# BAD.net
KiCad netlist of a schematic drawn in EAGLE
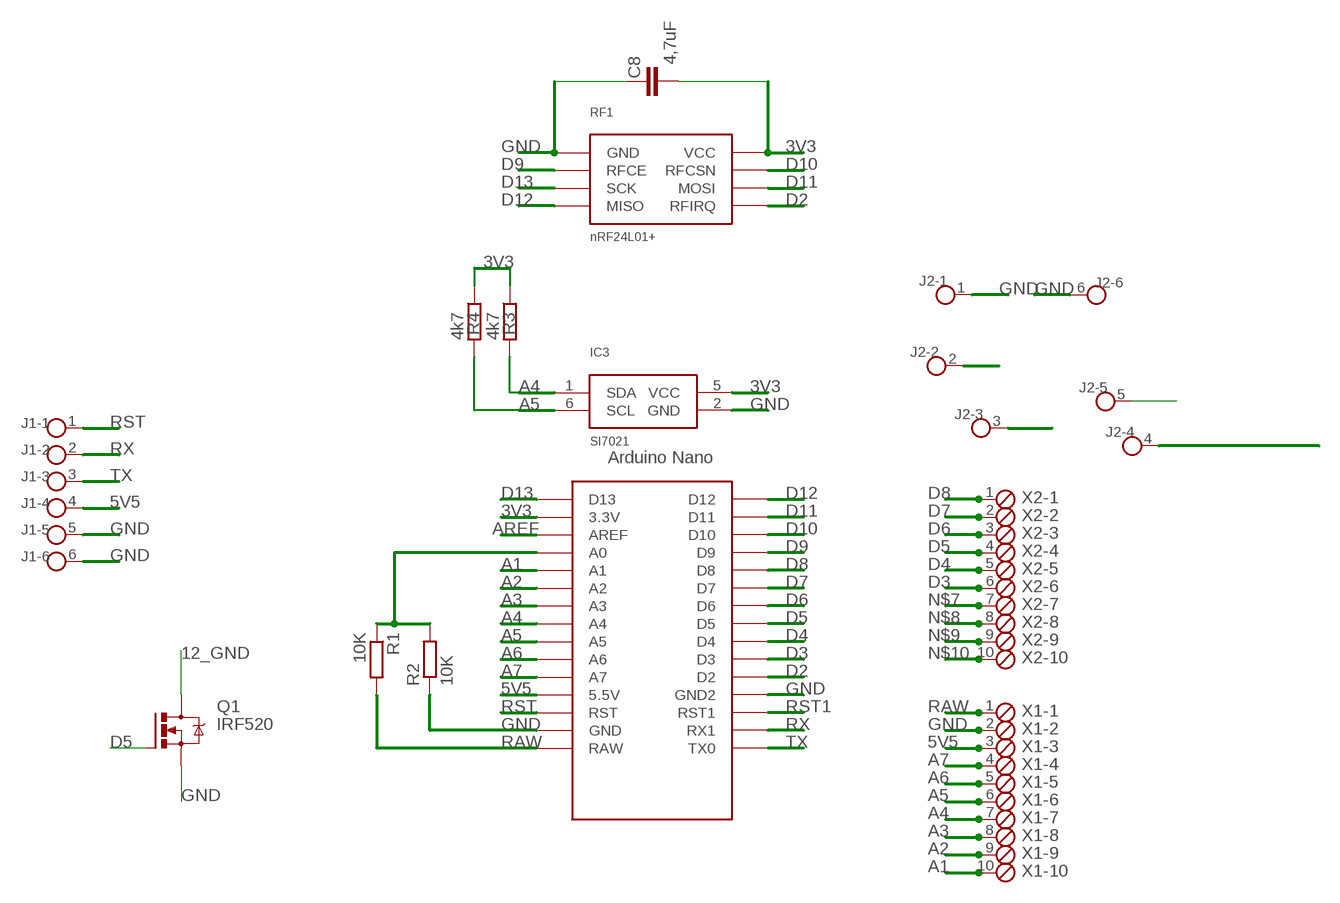
[diagram p0: schematic, sheet 1]

(export (version "E")
  (design (tool "Eeschema 10.0.6"))
  (components
    (comp (ref "C8")
      (value "4,7uF")
      (footprint "eagle-import:C3216")
      (libsource (lib "eagle-import") (part "C-EUC3216"))
    )
    (comp (ref "IC3")
      (value "SI7021")
      (footprint "eagle-import:DFN6")
      (libsource (lib "eagle-import") (part "SI7021"))
    )
    (comp (ref "J1")
      (value "FTDI")
      (footprint "eagle-import:LIST6B")
      (libsource (lib "eagle-import") (part "LIST6LIST6B"))
    )
    (comp (ref "J2")
      (value "LIST6")
      (footprint "eagle-import:LIST6")
      (libsource (lib "eagle-import") (part "LIST6"))
    )
    (comp (ref "Q1")
      (value "IRF520")
      (footprint "eagle-import:TO220BV")
      (libsource (lib "eagle-import") (part "IRF520"))
    )
    (comp (ref "R1")
      (value "10K")
      (footprint "eagle-import:R0805")
      (libsource (lib "eagle-import") (part "R-EU_R0805"))
    )
    (comp (ref "R2")
      (value "10K")
      (footprint "eagle-import:R0805")
      (libsource (lib "eagle-import") (part "R-EU_R0805"))
    )
    (comp (ref "R3")
      (value "4k7")
      (footprint "eagle-import:R0805")
      (libsource (lib "eagle-import") (part "R-EU_R0805"))
    )
    (comp (ref "R4")
      (value "4k7")
      (footprint "eagle-import:R0805")
      (libsource (lib "eagle-import") (part "R-EU_R0805"))
    )
    (comp (ref "RF1")
      (value "nRF24L01+")
      (footprint "eagle-import:2X4-2.54MM")
      (libsource (lib "eagle-import") (part "NRF24L01"))
    )
    (comp (ref "U$1")
      (value "NANO")
      (footprint "eagle-import:NANO")
      (libsource (lib "eagle-import") (part "NANO"))
    )
    (comp (ref "X1")
      (value "MPT10")
      (footprint "eagle-import:10POL254")
      (libsource (lib "eagle-import") (part "MPT10"))
    )
    (comp (ref "X2")
      (value "MPT10")
      (footprint "eagle-import:10POL254")
      (libsource (lib "eagle-import") (part "MPT10"))
    )
  )
  (nets
    (net (code "1") (name "/3V3") (class "Default")
      (node (ref "C8") (pin "1") (pinfunction "1_1") (pintype "passive"))
      (node (ref "IC3") (pin "5") (pinfunction "VCC_5") (pintype "bidirectional"))
      (node (ref "J2") (pin "2") (pinfunction "1_2") (pintype "passive"))
      (node (ref "R3") (pin "1") (pinfunction "1_1") (pintype "passive"))
      (node (ref "R4") (pin "1") (pinfunction "1_1") (pintype "passive"))
      (node (ref "RF1") (pin "P$2") (pinfunction "VCC_P$2") (pintype "power_in"))
      (node (ref "U$1") (pin "3.3V") (pinfunction "3.3V_3.3V") (pintype "bidirectional"))
    )
    (net (code "2") (name "/5V5") (class "Default")
      (node (ref "J1") (pin "4") (pinfunction "1_4") (pintype "passive"))
      (node (ref "J2") (pin "3") (pinfunction "1_3") (pintype "passive"))
      (node (ref "U$1") (pin "5V") (pinfunction "5.5V_5V") (pintype "bidirectional"))
      (node (ref "X1") (pin "3") (pinfunction "1_3") (pintype "passive"))
    )
    (net (code "3") (name "/12_GND") (class "Default")
      (node (ref "J2") (pin "5") (pinfunction "1_5") (pintype "passive"))
      (node (ref "Q1") (pin "D") (pinfunction "D_D") (pintype "passive"))
    )
    (net (code "4") (name "/A1") (class "Default")
      (node (ref "U$1") (pin "A1") (pinfunction "A1_A1") (pintype "bidirectional"))
      (node (ref "X1") (pin "10") (pinfunction "1_10") (pintype "passive"))
    )
    (net (code "5") (name "/A2") (class "Default")
      (node (ref "U$1") (pin "A2") (pinfunction "A2_A2") (pintype "bidirectional"))
      (node (ref "X1") (pin "9") (pinfunction "1_9") (pintype "passive"))
    )
    (net (code "6") (name "/A3") (class "Default")
      (node (ref "U$1") (pin "A3") (pinfunction "A3_A3") (pintype "bidirectional"))
      (node (ref "X1") (pin "8") (pinfunction "1_8") (pintype "passive"))
    )
    (net (code "7") (name "/A4") (class "Default")
      (node (ref "IC3") (pin "1") (pinfunction "SDA_1") (pintype "bidirectional"))
      (node (ref "R3") (pin "2") (pinfunction "2_2") (pintype "passive"))
      (node (ref "U$1") (pin "A4") (pinfunction "A4_A4") (pintype "bidirectional"))
      (node (ref "X1") (pin "7") (pinfunction "1_7") (pintype "passive"))
    )
    (net (code "8") (name "/A5") (class "Default")
      (node (ref "IC3") (pin "6") (pinfunction "SCL_6") (pintype "bidirectional"))
      (node (ref "R4") (pin "2") (pinfunction "2_2") (pintype "passive"))
      (node (ref "U$1") (pin "A5") (pinfunction "A5_A5") (pintype "bidirectional"))
      (node (ref "X1") (pin "6") (pinfunction "1_6") (pintype "passive"))
    )
    (net (code "9") (name "/A6") (class "Default")
      (node (ref "U$1") (pin "A6") (pinfunction "A6_A6") (pintype "bidirectional"))
      (node (ref "X1") (pin "5") (pinfunction "1_5") (pintype "passive"))
    )
    (net (code "10") (name "/A7") (class "Default")
      (node (ref "U$1") (pin "A7") (pinfunction "A7_A7") (pintype "bidirectional"))
      (node (ref "X1") (pin "4") (pinfunction "1_4") (pintype "passive"))
    )
    (net (code "11") (name "/AREF") (class "Default")
      (node (ref "U$1") (pin "AREF") (pinfunction "AREF_AREF") (pintype "bidirectional"))
    )
    (net (code "12") (name "/D2") (class "Default")
      (node (ref "RF1") (pin "P$8") (pinfunction "RFIRQ_P$8") (pintype "output"))
      (node (ref "U$1") (pin "D2") (pinfunction "D2_D2") (pintype "bidirectional"))
    )
    (net (code "13") (name "/D3") (class "Default")
      (node (ref "U$1") (pin "D3") (pinfunction "D3_D3") (pintype "bidirectional"))
      (node (ref "X2") (pin "6") (pinfunction "1_6") (pintype "passive"))
    )
    (net (code "14") (name "/D4") (class "Default")
      (node (ref "U$1") (pin "D4") (pinfunction "D4_D4") (pintype "bidirectional"))
      (node (ref "X2") (pin "5") (pinfunction "1_5") (pintype "passive"))
    )
    (net (code "15") (name "/D5") (class "Default")
      (node (ref "Q1") (pin "G") (pinfunction "G_G") (pintype "passive"))
      (node (ref "U$1") (pin "D5") (pinfunction "D5_D5") (pintype "bidirectional"))
      (node (ref "X2") (pin "4") (pinfunction "1_4") (pintype "passive"))
    )
    (net (code "16") (name "/D6") (class "Default")
      (node (ref "U$1") (pin "D6") (pinfunction "D6_D6") (pintype "bidirectional"))
      (node (ref "X2") (pin "3") (pinfunction "1_3") (pintype "passive"))
    )
    (net (code "17") (name "/D7") (class "Default")
      (node (ref "U$1") (pin "D7") (pinfunction "D7_D7") (pintype "bidirectional"))
      (node (ref "X2") (pin "2") (pinfunction "1_2") (pintype "passive"))
    )
    (net (code "18") (name "/D8") (class "Default")
      (node (ref "U$1") (pin "D8") (pinfunction "D8_D8") (pintype "bidirectional"))
      (node (ref "X2") (pin "1") (pinfunction "1_1") (pintype "passive"))
    )
    (net (code "19") (name "/D9") (class "Default")
      (node (ref "RF1") (pin "P$3") (pinfunction "RFCE_P$3") (pintype "input"))
      (node (ref "U$1") (pin "D9") (pinfunction "D9_D9") (pintype "bidirectional"))
    )
    (net (code "20") (name "/D10") (class "Default")
      (node (ref "RF1") (pin "P$4") (pinfunction "RFCSN_P$4") (pintype "bidirectional"))
      (node (ref "U$1") (pin "D10") (pinfunction "D10_D10") (pintype "bidirectional"))
    )
    (net (code "21") (name "/D11") (class "Default")
      (node (ref "RF1") (pin "P$6") (pinfunction "MOSI_P$6") (pintype "bidirectional"))
      (node (ref "U$1") (pin "D11") (pinfunction "D11_D11") (pintype "bidirectional"))
    )
    (net (code "22") (name "/D12") (class "Default")
      (node (ref "RF1") (pin "P$7") (pinfunction "MISO_P$7") (pintype "bidirectional"))
      (node (ref "U$1") (pin "D12") (pinfunction "D12_D12") (pintype "bidirectional"))
    )
    (net (code "23") (name "/D13") (class "Default")
      (node (ref "RF1") (pin "P$5") (pinfunction "SCK_P$5") (pintype "input"))
      (node (ref "U$1") (pin "D13") (pinfunction "D13_D13") (pintype "bidirectional"))
    )
    (net (code "24") (name "/GND") (class "Default")
      (node (ref "C8") (pin "2") (pinfunction "2_2") (pintype "passive"))
      (node (ref "IC3") (pin "2") (pinfunction "GND_2") (pintype "bidirectional"))
      (node (ref "J1") (pin "5") (pinfunction "1_5") (pintype "passive"))
      (node (ref "J1") (pin "6") (pinfunction "1_6") (pintype "passive"))
      (node (ref "J2") (pin "1") (pinfunction "1_1") (pintype "passive"))
      (node (ref "J2") (pin "6") (pinfunction "1_6") (pintype "passive"))
      (node (ref "Q1") (pin "S") (pinfunction "S_S") (pintype "passive"))
      (node (ref "R2") (pin "1") (pinfunction "1_1") (pintype "passive"))
      (node (ref "RF1") (pin "P$1") (pinfunction "GND_P$1") (pintype "power_in"))
      (node (ref "U$1") (pin "GND") (pinfunction "GND_GND") (pintype "bidirectional"))
      (node (ref "U$1") (pin "GND1") (pinfunction "GND2_GND1") (pintype "bidirectional"))
      (node (ref "X1") (pin "2") (pinfunction "1_2") (pintype "passive"))
    )
    (net (code "25") (name "/N$7") (class "Default")
      (node (ref "X2") (pin "7") (pinfunction "1_7") (pintype "passive"))
    )
    (net (code "26") (name "/N$8") (class "Default")
      (node (ref "X2") (pin "8") (pinfunction "1_8") (pintype "passive"))
    )
    (net (code "27") (name "/N$9") (class "Default")
      (node (ref "X2") (pin "9") (pinfunction "1_9") (pintype "passive"))
    )
    (net (code "28") (name "/N$10") (class "Default")
      (node (ref "X2") (pin "10") (pinfunction "1_10") (pintype "passive"))
    )
    (net (code "29") (name "/RAW") (class "Default")
      (node (ref "J2") (pin "4") (pinfunction "1_4") (pintype "passive"))
      (node (ref "R1") (pin "2") (pinfunction "2_2") (pintype "passive"))
      (node (ref "U$1") (pin "RAW") (pinfunction "RAW_RAW") (pintype "bidirectional"))
      (node (ref "X1") (pin "1") (pinfunction "1_1") (pintype "passive"))
    )
    (net (code "30") (name "/RST") (class "Default")
      (node (ref "J1") (pin "1") (pinfunction "1_1") (pintype "passive"))
      (node (ref "U$1") (pin "RST") (pinfunction "RST_RST") (pintype "bidirectional"))
    )
    (net (code "31") (name "/RST1") (class "Default")
      (node (ref "U$1") (pin "RST1") (pinfunction "RST1_RST1") (pintype "bidirectional"))
    )
    (net (code "32") (name "/RX") (class "Default")
      (node (ref "J1") (pin "2") (pinfunction "1_2") (pintype "passive"))
      (node (ref "U$1") (pin "RX1") (pinfunction "RX1_RX1") (pintype "bidirectional"))
    )
    (net (code "33") (name "/TX") (class "Default")
      (node (ref "J1") (pin "3") (pinfunction "1_3") (pintype "passive"))
      (node (ref "U$1") (pin "TX0") (pinfunction "TX0_TX0") (pintype "bidirectional"))
    )
    (net (code "34") (name "Net-(R1-Pad1)") (class "Default")
      (node (ref "R1") (pin "1") (pinfunction "1_1") (pintype "passive"))
      (node (ref "R2") (pin "2") (pinfunction "2_2") (pintype "passive"))
      (node (ref "U$1") (pin "A0") (pinfunction "A0_A0") (pintype "bidirectional"))
    )
    (net (code "35") (name "unconnected-(U$1-PadICSP1)") (class "Default")
      (node (ref "U$1") (pin "ICSP1") (pinfunction "ICSP1_ICSP1") (pintype "bidirectional"))
    )
    (net (code "36") (name "unconnected-(U$1-PadICSP2)") (class "Default")
      (node (ref "U$1") (pin "ICSP2") (pinfunction "ICSP2_ICSP2") (pintype "bidirectional"))
    )
    (net (code "37") (name "unconnected-(U$1-PadICSP3)") (class "Default")
      (node (ref "U$1") (pin "ICSP3") (pinfunction "ICSP3_ICSP3") (pintype "bidirectional"))
    )
    (net (code "38") (name "unconnected-(U$1-PadICSP4)") (class "Default")
      (node (ref "U$1") (pin "ICSP4") (pinfunction "ICSP4_ICSP4") (pintype "bidirectional"))
    )
    (net (code "39") (name "unconnected-(U$1-PadICSP5)") (class "Default")
      (node (ref "U$1") (pin "ICSP5") (pinfunction "ICSP5_ICSP5") (pintype "bidirectional"))
    )
    (net (code "40") (name "unconnected-(U$1-PadICSP6)") (class "Default")
      (node (ref "U$1") (pin "ICSP6") (pinfunction "ICSP6_ICSP6") (pintype "bidirectional"))
    )
  )
)
